# mixer_30mil_1GHz.net
KiCad netlist of a schematic drawn in Altium Designer
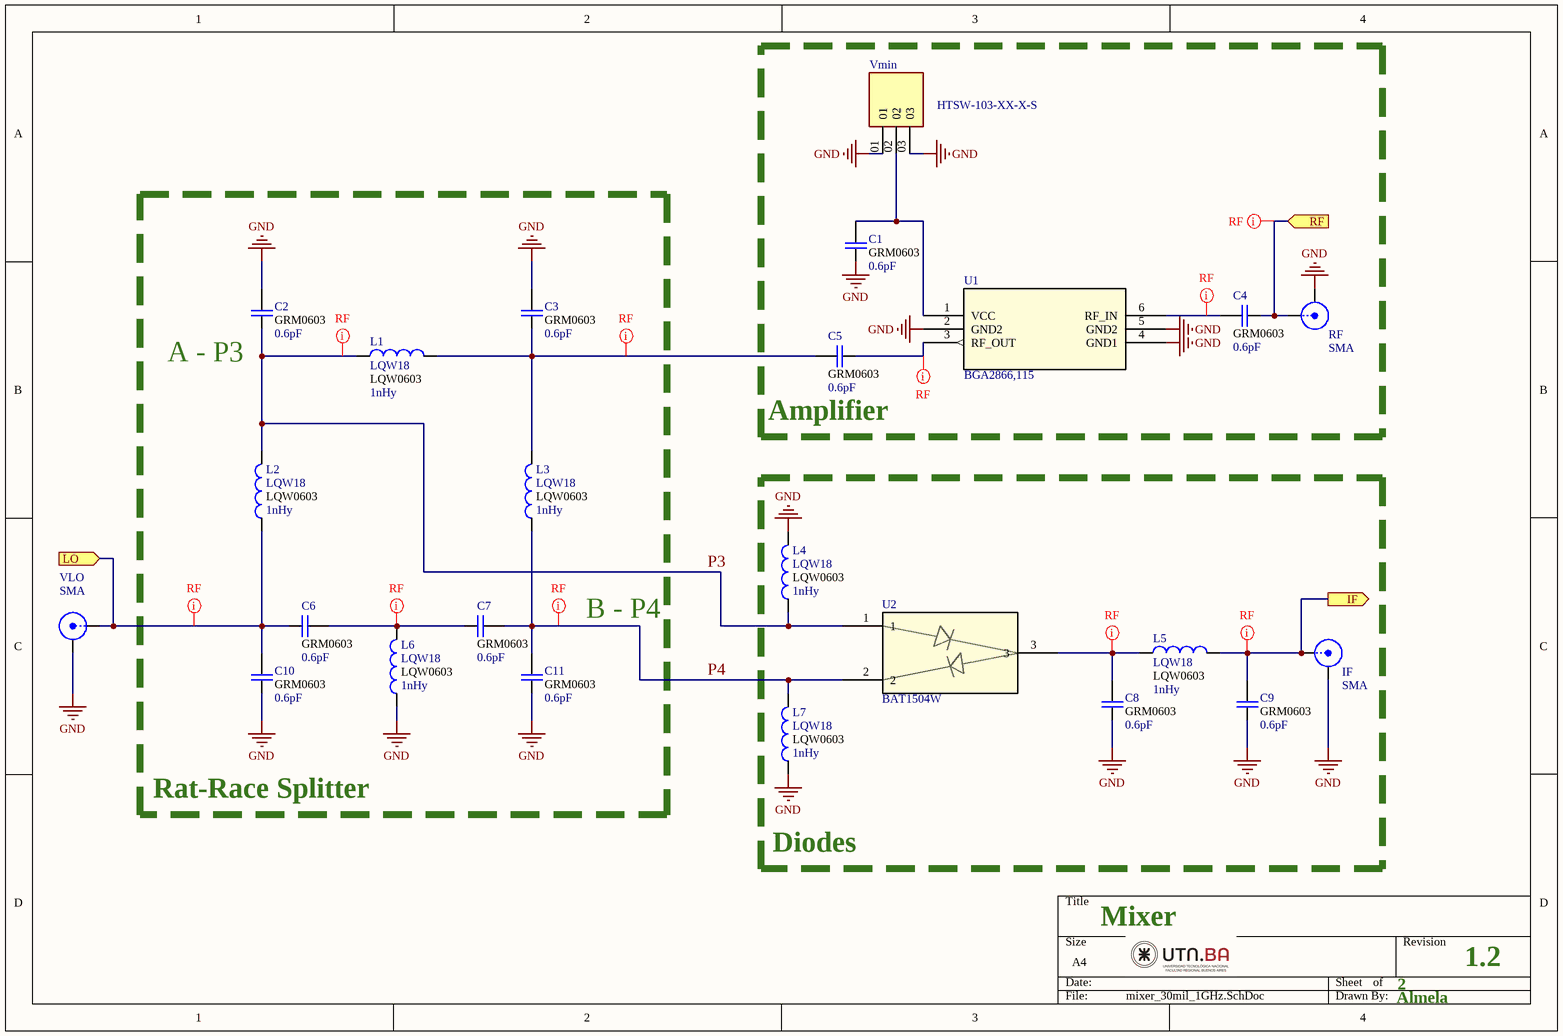
[diagram p0: mixer_30mil_1GHz.SchDoc]

(export (version "E")
  (design (tool "Eeschema 10.0.6"))
  (components
    (comp (ref "C1")
      (value "0.6pF")
      (footprint "GRM0603")
      (description "Capacitor GRM18 0603")
      (fields (field (name "Comment") "Cap 0603") (field (name "PUBLISHER") "Altium Limited"))
      (libsource (lib "Radar_RF_EAIII") (part "Cap"))
    )
    (comp (ref "C2")
      (value "0.6pF")
      (footprint "GRM0603")
      (description "Capacitor GRM18 0603")
      (fields (field (name "Comment") "Cap 0603") (field (name "PUBLISHER") "Altium Limited"))
      (libsource (lib "Radar_RF_EAIII") (part "Cap"))
    )
    (comp (ref "C3")
      (value "0.6pF")
      (footprint "GRM0603")
      (description "Capacitor GRM18 0603")
      (fields (field (name "Comment") "Cap 0603") (field (name "PUBLISHER") "Altium Limited"))
      (libsource (lib "Radar_RF_EAIII") (part "Cap"))
    )
    (comp (ref "C4")
      (value "0.6pF")
      (footprint "GRM0603")
      (description "Capacitor GRM18 0603")
      (fields (field (name "Comment") "Cap 0603") (field (name "PUBLISHER") "Altium Limited"))
      (libsource (lib "Radar_RF_EAIII") (part "Cap"))
    )
    (comp (ref "C5")
      (value "0.6pF")
      (footprint "GRM0603")
      (description "Capacitor GRM18 0603")
      (fields (field (name "Comment") "Cap 0603") (field (name "PUBLISHER") "Altium Limited"))
      (libsource (lib "Radar_RF_EAIII") (part "Cap"))
    )
    (comp (ref "C6")
      (value "0.6pF")
      (footprint "GRM0603")
      (description "Capacitor GRM18 0603")
      (fields (field (name "Comment") "Cap 0603") (field (name "PUBLISHER") "Altium Limited"))
      (libsource (lib "Radar_RF_EAIII") (part "Cap"))
    )
    (comp (ref "C7")
      (value "0.6pF")
      (footprint "GRM0603")
      (description "Capacitor GRM18 0603")
      (fields (field (name "Comment") "Cap 0603") (field (name "PUBLISHER") "Altium Limited"))
      (libsource (lib "Radar_RF_EAIII") (part "Cap"))
    )
    (comp (ref "C8")
      (value "0.6pF")
      (footprint "GRM0603")
      (description "Capacitor GRM18 0603")
      (fields (field (name "Comment") "Cap 0603") (field (name "PUBLISHER") "Altium Limited"))
      (libsource (lib "Radar_RF_EAIII") (part "Cap"))
    )
    (comp (ref "C9")
      (value "0.6pF")
      (footprint "GRM0603")
      (description "Capacitor GRM18 0603")
      (fields (field (name "Comment") "Cap 0603") (field (name "PUBLISHER") "Altium Limited"))
      (libsource (lib "Radar_RF_EAIII") (part "Cap"))
    )
    (comp (ref "C10")
      (value "0.6pF")
      (footprint "GRM0603")
      (description "Capacitor GRM18 0603")
      (fields (field (name "Comment") "Cap 0603") (field (name "PUBLISHER") "Altium Limited"))
      (libsource (lib "Radar_RF_EAIII") (part "Cap"))
    )
    (comp (ref "C11")
      (value "0.6pF")
      (footprint "GRM0603")
      (description "Capacitor GRM18 0603")
      (fields (field (name "Comment") "Cap 0603") (field (name "PUBLISHER") "Altium Limited"))
      (libsource (lib "Radar_RF_EAIII") (part "Cap"))
    )
    (comp (ref "IF")
      (value "SMA")
      (footprint "SMA-142-0701-851")
      (description "SMB Straight Connector")
      (fields (field (name "PUBLISHER") "Altium Limited"))
      (libsource (lib "PCB_Project") (part "SMB"))
    )
    (comp (ref "L1")
      (value "LQW18")
      (footprint "INDC1608X100N")
      (description "Ind RF Chip Wirewound 18nH 5% 100MHz 40Q-Factor 550mA 0603 Paper T/R")
      (fields
        (field (name "MP") "LQW18AN18NJ00D")
        (field (name "PARAMETER 1") "LQW0603")
        (field (name "ALTIUM_VALUE") "1nHy")
      )
      (libsource (lib "Radar_RF_EAIII") (part "LQW18"))
    )
    (comp (ref "L2")
      (value "LQW18")
      (footprint "INDC1608X100N")
      (description "Ind RF Chip Wirewound 18nH 5% 100MHz 40Q-Factor 550mA 0603 Paper T/R")
      (fields
        (field (name "MP") "LQW18AN18NJ00D")
        (field (name "PARAMETER 1") "LQW0603")
        (field (name "ALTIUM_VALUE") "1nHy")
      )
      (libsource (lib "Radar_RF_EAIII") (part "LQW18"))
    )
    (comp (ref "L3")
      (value "LQW18")
      (footprint "INDC1608X100N")
      (description "Ind RF Chip Wirewound 18nH 5% 100MHz 40Q-Factor 550mA 0603 Paper T/R")
      (fields
        (field (name "MP") "LQW18AN18NJ00D")
        (field (name "PARAMETER 1") "LQW0603")
        (field (name "ALTIUM_VALUE") "1nHy")
      )
      (libsource (lib "Radar_RF_EAIII") (part "LQW18"))
    )
    (comp (ref "L4")
      (value "LQW18")
      (footprint "INDC1608X100N")
      (description "Ind RF Chip Wirewound 18nH 5% 100MHz 40Q-Factor 550mA 0603 Paper T/R")
      (fields
        (field (name "MP") "LQW18AN18NJ00D")
        (field (name "PARAMETER 1") "LQW0603")
        (field (name "ALTIUM_VALUE") "1nHy")
      )
      (libsource (lib "Radar_RF_EAIII") (part "LQW18"))
    )
    (comp (ref "L5")
      (value "LQW18")
      (footprint "INDC1608X100N")
      (description "Ind RF Chip Wirewound 18nH 5% 100MHz 40Q-Factor 550mA 0603 Paper T/R")
      (fields
        (field (name "MP") "LQW18AN18NJ00D")
        (field (name "PARAMETER 1") "LQW0603")
        (field (name "ALTIUM_VALUE") "1nHy")
      )
      (libsource (lib "Radar_RF_EAIII") (part "LQW18"))
    )
    (comp (ref "L6")
      (value "LQW18")
      (footprint "INDC1608X100N")
      (description "Ind RF Chip Wirewound 18nH 5% 100MHz 40Q-Factor 550mA 0603 Paper T/R")
      (fields
        (field (name "MP") "LQW18AN18NJ00D")
        (field (name "PARAMETER 1") "LQW0603")
        (field (name "ALTIUM_VALUE") "1nHy")
      )
      (libsource (lib "Radar_RF_EAIII") (part "LQW18"))
    )
    (comp (ref "L7")
      (value "LQW18")
      (footprint "INDC1608X100N")
      (description "Ind RF Chip Wirewound 18nH 5% 100MHz 40Q-Factor 550mA 0603 Paper T/R")
      (fields
        (field (name "MP") "LQW18AN18NJ00D")
        (field (name "PARAMETER 1") "LQW0603")
        (field (name "ALTIUM_VALUE") "1nHy")
      )
      (libsource (lib "Radar_RF_EAIII") (part "LQW18"))
    )
    (comp (ref "RF")
      (value "SMA")
      (footprint "SMA-142-0701-851")
      (description "SMB Straight Connector")
      (fields (field (name "PUBLISHER") "Altium Limited"))
      (libsource (lib "PCB_Project") (part "SMB"))
    )
    (comp (ref "U1")
      (value "BGA2866,115")
      (footprint "SOT363_NXP")
      (description "No Description Available")
      (libsource (lib "Radar_RF_EAIII") (part "BGA2866,115"))
    )
    (comp (ref "U2")
      (value "BAT1504W")
      (footprint "SOT_327XTSA1_INF")
      (description "Diodo")
      (libsource (lib "Radar_RF_EAIII") (part "BAT1504W"))
    )
    (comp (ref "VLO")
      (value "SMA")
      (footprint "SMA-142-0701-851")
      (description "SMB Straight Connector")
      (fields (field (name "PUBLISHER") "Altium Limited"))
      (libsource (lib "PCB_Project") (part "SMB"))
    )
    (comp (ref "Vmin")
      (value "HTSW-103-XX-X-S")
      (footprint "SAMTEC_HTSW-103-XX-X-S")
      (description "Conn Unshrouded Header HDR 3 POS 2.54mm Solder ST Top Entry Thru-Hole Bag")
      (fields (field (name "MP") "HTSW-103-08-S-S") (field (name "MF") "Samtec"))
      (libsource (lib "HTSW-103-XX-X-S") (part "HTSW-103-XX-X-S"))
    )
  )
  (nets
    (net (code "1") (name "/IF") (class "Default")
      (node (ref "C9") (pin "2") (pinfunction "2_2") (pintype "passive"))
      (node (ref "IF") (pin "1") (pinfunction "X_1") (pintype "passive"))
      (node (ref "L5") (pin "2") (pinfunction "2_2") (pintype "passive"))
    )
    (net (code "2") (name "/LO") (class "Default")
      (node (ref "C10") (pin "2") (pinfunction "2_2") (pintype "passive"))
      (node (ref "C6") (pin "1") (pinfunction "1_1") (pintype "passive"))
      (node (ref "L2") (pin "1") (pinfunction "1_1") (pintype "passive"))
      (node (ref "VLO") (pin "1") (pinfunction "X_1") (pintype "passive"))
    )
    (net (code "3") (name "/P3") (class "Default")
      (node (ref "C2") (pin "1") (pinfunction "1_1") (pintype "passive"))
      (node (ref "L1") (pin "1") (pinfunction "1_1") (pintype "passive"))
      (node (ref "L2") (pin "2") (pinfunction "2_2") (pintype "passive"))
      (node (ref "L4") (pin "1") (pinfunction "1_1") (pintype "passive"))
      (node (ref "U2") (pin "1") (pinfunction "1_1") (pintype "passive"))
    )
    (net (code "4") (name "/P4") (class "Default")
      (node (ref "C11") (pin "2") (pinfunction "2_2") (pintype "passive"))
      (node (ref "C7") (pin "2") (pinfunction "2_2") (pintype "passive"))
      (node (ref "L3") (pin "1") (pinfunction "1_1") (pintype "passive"))
      (node (ref "L7") (pin "2") (pinfunction "2_2") (pintype "passive"))
      (node (ref "U2") (pin "2") (pinfunction "2_2") (pintype "passive"))
    )
    (net (code "5") (name "/RF") (class "Default")
      (node (ref "C4") (pin "1") (pinfunction "1_1") (pintype "passive"))
      (node (ref "RF") (pin "1") (pinfunction "X_1") (pintype "passive"))
    )
    (net (code "6") (name "GND") (class "Default")
      (node (ref "C1") (pin "1") (pinfunction "1_1") (pintype "passive"))
      (node (ref "C10") (pin "1") (pinfunction "1_1") (pintype "passive"))
      (node (ref "C11") (pin "1") (pinfunction "1_1") (pintype "passive"))
      (node (ref "C2") (pin "2") (pinfunction "2_2") (pintype "passive"))
      (node (ref "C3") (pin "2") (pinfunction "2_2") (pintype "passive"))
      (node (ref "C8") (pin "1") (pinfunction "1_1") (pintype "passive"))
      (node (ref "C9") (pin "1") (pinfunction "1_1") (pintype "passive"))
      (node (ref "IF") (pin "2") (pinfunction "Y_2") (pintype "passive"))
      (node (ref "L4") (pin "2") (pinfunction "2_2") (pintype "passive"))
      (node (ref "L6") (pin "1") (pinfunction "1_1") (pintype "passive"))
      (node (ref "L7") (pin "1") (pinfunction "1_1") (pintype "passive"))
      (node (ref "RF") (pin "2") (pinfunction "Y_2") (pintype "passive"))
      (node (ref "U1") (pin "2") (pinfunction "GND2_2") (pintype "power_in"))
      (node (ref "U1") (pin "4") (pinfunction "GND1_4") (pintype "power_in"))
      (node (ref "U1") (pin "5") (pinfunction "GND2_5") (pintype "power_in"))
      (node (ref "VLO") (pin "2") (pinfunction "Y_2") (pintype "passive"))
      (node (ref "Vmin") (pin "01") (pinfunction "01_01") (pintype "passive"))
      (node (ref "Vmin") (pin "03") (pinfunction "03_03") (pintype "passive"))
    )
    (net (code "7") (name "Net-(C3-Pad1)") (class "Default")
      (node (ref "C3") (pin "1") (pinfunction "1_1") (pintype "passive"))
      (node (ref "C5") (pin "2") (pinfunction "2_2") (pintype "passive"))
      (node (ref "L1") (pin "2") (pinfunction "2_2") (pintype "passive"))
      (node (ref "L3") (pin "2") (pinfunction "2_2") (pintype "passive"))
    )
    (net (code "8") (name "Net-(C6-Pad2)") (class "Default")
      (node (ref "C6") (pin "2") (pinfunction "2_2") (pintype "passive"))
      (node (ref "C7") (pin "1") (pinfunction "1_1") (pintype "passive"))
      (node (ref "L6") (pin "2") (pinfunction "2_2") (pintype "passive"))
    )
    (net (code "9") (name "Net-(C8-Pad2)") (class "Default")
      (node (ref "C8") (pin "2") (pinfunction "2_2") (pintype "passive"))
      (node (ref "L5") (pin "1") (pinfunction "1_1") (pintype "passive"))
      (node (ref "U2") (pin "3") (pinfunction "3_3") (pintype "passive"))
    )
    (net (code "10") (name "Net-(U1-RF_IN)") (class "Default")
      (node (ref "C4") (pin "2") (pinfunction "2_2") (pintype "passive"))
      (node (ref "U1") (pin "6") (pinfunction "RF_IN_6") (pintype "passive"))
    )
    (net (code "11") (name "Net-(U1-RF_OUT)") (class "Default")
      (node (ref "C5") (pin "1") (pinfunction "1_1") (pintype "passive"))
      (node (ref "U1") (pin "3") (pinfunction "RF_OUT_3") (pintype "output"))
    )
    (net (code "12") (name "Net-(U1-VCC)") (class "Default")
      (node (ref "C1") (pin "2") (pinfunction "2_2") (pintype "passive"))
      (node (ref "U1") (pin "1") (pinfunction "VCC_1") (pintype "power_in"))
      (node (ref "Vmin") (pin "02") (pinfunction "02_02") (pintype "passive"))
    )
  )
)
